# arduinoNano.net
KiCad netlist of a schematic drawn in Altium Designer
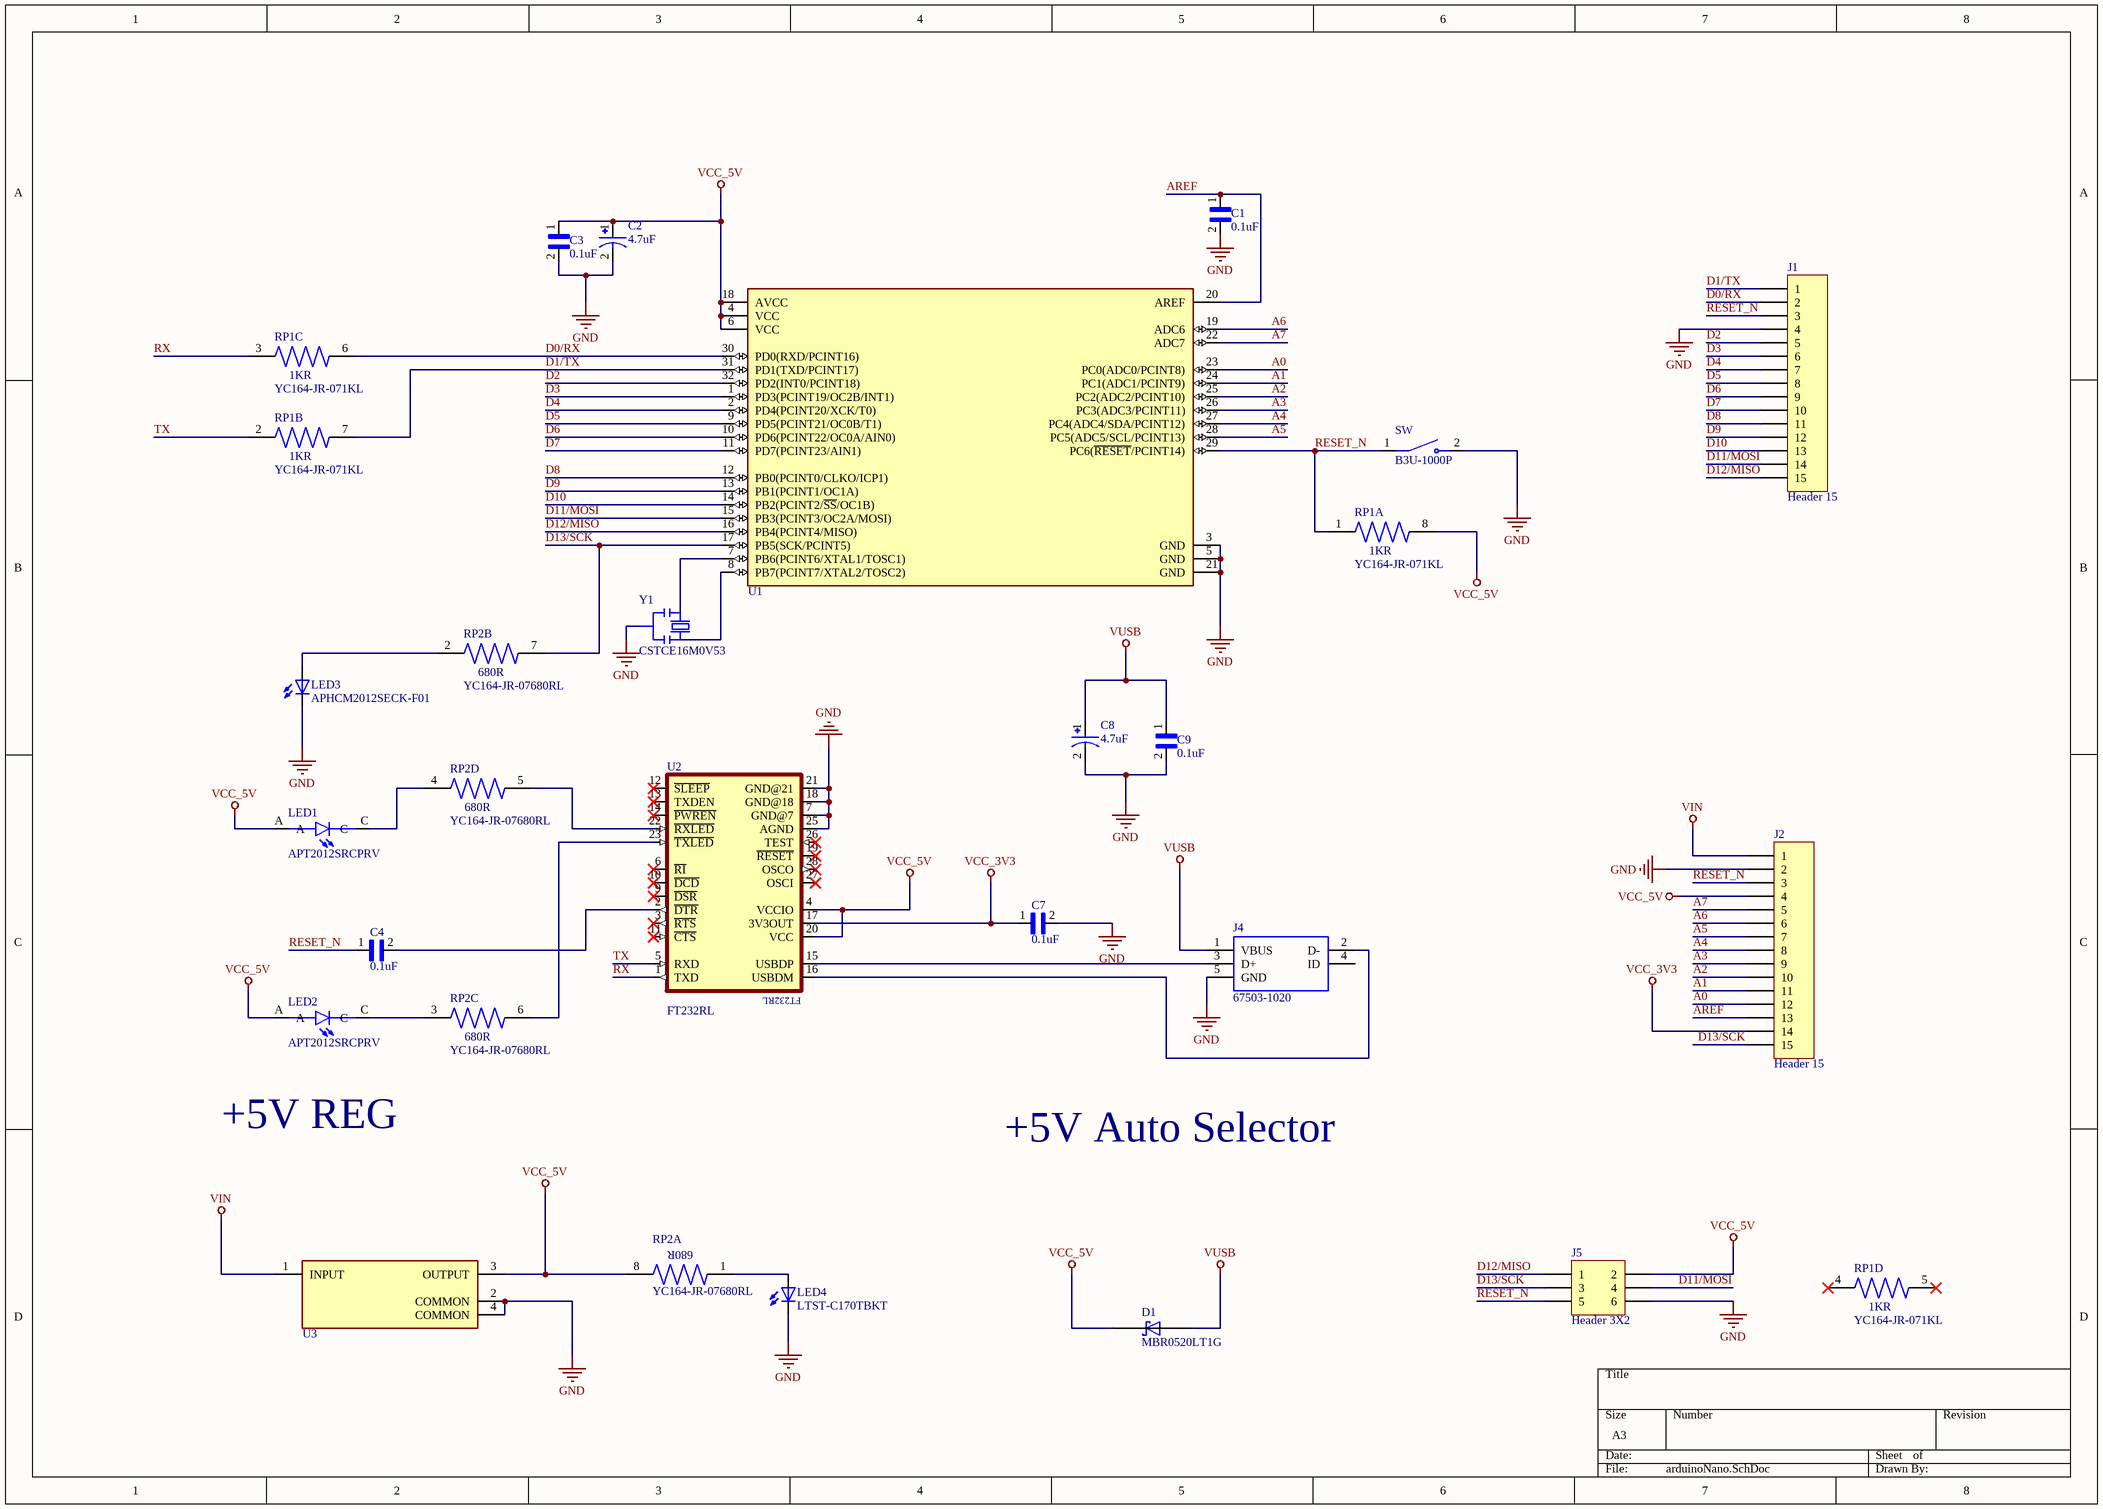
[diagram p0: arduinoNano.SchDoc]

(export (version "E")
  (design (tool "Eeschema 10.0.6"))
  (components
    (comp (ref "C1")
      (value "0.1uF")
      (footprint "arduino_nano:CAPC2012X88N")
      (description "SMD 0805 CERAMIC X7R -55^+125 100 NF +/-10? 50V")
      (fields (field (name "MF") "{'manufacturer': u'KEMET'}") (field (name "MP") "C0805C104K5RACTU"))
      (libsource (lib "arduino_nano") (part "C0805C104K5RACTU"))
    )
    (comp (ref "C2")
      (value "4.7uF")
      (footprint "arduino_nano:CAPMP3216X180N")
      (description "4.7ÂµF Molded Tantalum Capacitors 25V 1206 (3216 Metric) 6Ohm")
      (fields (field (name "MF") "{'manufacturer': u'KEMET'}") (field (name "MP") "T491A475K010AT"))
      (libsource (lib "arduino_nano") (part "T491A475K010AT"))
    )
    (comp (ref "C3")
      (value "0.1uF")
      (footprint "arduino_nano:CAPC2012X88N")
      (description "SMD 0805 CERAMIC X7R -55^+125 100 NF +/-10? 50V")
      (fields (field (name "MF") "{'manufacturer': u'KEMET'}") (field (name "MP") "C0805C104K5RACTU"))
      (libsource (lib "arduino_nano") (part "C0805C104K5RACTU"))
    )
    (comp (ref "C4")
      (value "0.1uF")
      (footprint "arduino_nano:CAPC2012X88N")
      (description "SMD 0805 CERAMIC X7R -55^+125 100 NF +/-10? 50V")
      (fields (field (name "MF") "{'manufacturer': u'KEMET'}") (field (name "MP") "C0805C104K5RACTU"))
      (libsource (lib "") (part "C0805C104K5RACTU_1"))
    )
    (comp (ref "C7")
      (value "0.1uF")
      (footprint "arduino_nano:CAPC2012X88N")
      (description "SMD 0805 CERAMIC X7R -55^+125 100 NF +/-10? 50V")
      (fields (field (name "MF") "{'manufacturer': u'KEMET'}") (field (name "MP") "C0805C104K5RACTU"))
      (libsource (lib "") (part "C0805C104K5RACTU_1"))
    )
    (comp (ref "C8")
      (value "4.7uF")
      (footprint "arduino_nano:CAPMP3216X180N")
      (description "4.7ÂµF Molded Tantalum Capacitors 25V 1206 (3216 Metric) 6Ohm")
      (fields (field (name "MF") "{'manufacturer': u'KEMET'}") (field (name "MP") "T491A475K010AT"))
      (libsource (lib "arduino_nano") (part "T491A475K010AT"))
    )
    (comp (ref "C9")
      (value "0.1uF")
      (footprint "arduino_nano:CAPC2012X88N")
      (description "SMD 0805 CERAMIC X7R -55^+125 100 NF +/-10? 50V")
      (fields (field (name "MF") "{'manufacturer': u'KEMET'}") (field (name "MP") "C0805C104K5RACTU"))
      (libsource (lib "arduino_nano") (part "C0805C104K5RACTU"))
    )
    (comp (ref "D1")
      (value "MBR0520LT1G")
      (footprint "arduino_nano:SOD3716X117(SOD-123)")
      (description "Surface Mount Schottky Power Rectifier Plastic SODâˆ’123 Package")
      (fields (field (name "MF") "{'manufacturer': u'ON Semiconductor'}"))
      (libsource (lib "arduino_nano") (part "MBR0520LT1G"))
    )
    (comp (ref "J1")
      (value "Header 15")
      (footprint "HDR1X15")
      (description "Header, 15-Pin")
      (fields (field (name "PUBLISHER") "Altium Limited"))
      (libsource (lib "Miscellaneous Connectors") (part "Header 15"))
    )
    (comp (ref "J2")
      (value "Header 15")
      (footprint "HDR1X15")
      (description "Header, 15-Pin")
      (fields (field (name "PUBLISHER") "Altium Limited"))
      (libsource (lib "Miscellaneous Connectors") (part "Header 15"))
    )
    (comp (ref "J4")
      (value "67503-1020")
      (footprint "arduino_nano:67503-1020")
      (fields (field (name "MF") "{'manufacturer': u'Molex'}"))
      (libsource (lib "arduino_nano") (part "67503-1020"))
    )
    (comp (ref "J5")
      (value "Header 3X2")
      (footprint "HDR2X3")
      (description "Header, 3-Pin, Dual row")
      (fields (field (name "PUBLISHER") "Altium Limited"))
      (libsource (lib "Miscellaneous Connectors") (part "Header 3X2"))
    )
    (comp (ref "LED1")
      (value "APT2012SRCPRV")
      (footprint "arduino_nano:LEDC2012X75N")
      (description "2.0X1.2MM,RED SMD LED")
      (fields (field (name "MF") "{'manufacturer': u'Kingbright'}"))
      (libsource (lib "arduino_nano") (part "APT2012SRCPRV"))
    )
    (comp (ref "LED2")
      (value "APT2012SRCPRV")
      (footprint "arduino_nano:LEDC2012X75N")
      (description "2.0X1.2MM,RED SMD LED")
      (fields (field (name "MF") "{'manufacturer': u'Kingbright'}"))
      (libsource (lib "arduino_nano") (part "APT2012SRCPRV"))
    )
    (comp (ref "LED3")
      (value "APHCM2012SECK-F01")
      (footprint "arduino_nano:DIOC200X125X110")
      (description "Green 2 x 1.25 x 1.1 mm 130Â° Water Clear 35 mcd 2 V Surface Mount LED")
      (fields (field (name "MF") "{'manufacturer': u'Lite-On Inc.'}") (field (name "MP") "LTST-C170TBKT"))
      (libsource (lib "arduino_nano") (part "LTST-C170TBKT"))
    )
    (comp (ref "LED4")
      (value "LTST-C170TBKT")
      (footprint "arduino_nano:DIOC200X125X110")
      (description "Green 2 x 1.25 x 1.1 mm 130Â° Water Clear 35 mcd 2 V Surface Mount LED")
      (fields (field (name "MF") "{'manufacturer': u'Lite-On Inc.'}"))
      (libsource (lib "arduino_nano") (part "LTST-C170TBKT"))
    )
    (comp (ref "RP1")
      (value "YC164-JR-071KL")
      (footprint "RESCAXE80P320X160X70-8N")
      (description "Res Thick Film Array 100 Ohm 5% ?200ppm/C ISOL Epoxy 8-Pin 1206(4 X 0603) Convex SMD T/R")
      (libsource (lib "arduino_nano") (part "YC164-JR-071KL"))
    )
    (comp (ref "RP2")
      (value "YC164-JR-07680RL")
      (footprint "RESCAXE80P320X160X70-8N")
      (description "Res Thick Film Array 100 Ohm 5% ?200ppm/C ISOL Epoxy 8-Pin 1206(4 X 0603) Convex SMD T/R")
      (libsource (lib "arduino_nano") (part "YC164-JR-07680RL"))
    )
    (comp (ref "SW")
      (value "B3U-1000P")
      (footprint "arduino_nano:SW_B3U-1000P")
      (description "Switch Tactile N.O. SPST Round Button Gull Wing 0.05A 12VDC 1.5N SMD Embossed T/R")
      (fields (field (name "MF") "{'manufacturer': u'Omron'}"))
      (libsource (lib "arduino_nano") (part "B3U-1000P"))
    )
    (comp (ref "U1")
      (value "ATMEGA168-20AU")
      (footprint "Microchip_32A_IPC_A")
      (libsource (lib "arduino_nano") (part "ATMEGA168-20AU"))
    )
    (comp (ref "U2")
      (value "FT232RL")
      (footprint "arduino_nano:SSOP28-0.65-10.2X5.2MM")
      (fields (field (name "MF") "{'manufacturer': u'FTDI, Future'}"))
      (libsource (lib "arduino_nano") (part "FT232RL"))
    )
    (comp (ref "U3")
      (value "UA78M05CDCYRG3")
      (footprint "Texas_Instruments_DCY0004A_IPC_A")
      (libsource (lib "arduino_nano") (part "UA78M05CDCYRG3"))
    )
    (comp (ref "Y1")
      (value "CSTCE16M0V53")
      (footprint "arduino_nano:CSTCE16M0V53")
      (description "<b>CSTCE16M0V53</b> Ceramic Resonator (CERALOCK) 16 MHz Chip Type")
      (fields (field (name "MF") "{'manufacturer': u'Murata Electronics'}"))
      (libsource (lib "arduino_nano") (part "CSTCE16M0V53"))
    )
  )
  (nets
    (net (code "1") (name "/A0") (class "Default")
      (node (ref "J2") (pin "12") (pinfunction "12_12") (pintype "passive"))
      (node (ref "U1") (pin "23") (pinfunction "PC0(ADC0/PCINT8)_23") (pintype "bidirectional"))
    )
    (net (code "2") (name "/A1") (class "Default")
      (node (ref "J2") (pin "11") (pinfunction "11_11") (pintype "passive"))
      (node (ref "U1") (pin "24") (pinfunction "PC1(ADC1/PCINT9)_24") (pintype "bidirectional"))
    )
    (net (code "3") (name "/A2") (class "Default")
      (node (ref "J2") (pin "10") (pinfunction "10_10") (pintype "passive"))
      (node (ref "U1") (pin "25") (pinfunction "PC2(ADC2/PCINT10)_25") (pintype "bidirectional"))
    )
    (net (code "4") (name "/A3") (class "Default")
      (node (ref "J2") (pin "9") (pinfunction "9_9") (pintype "passive"))
      (node (ref "U1") (pin "26") (pinfunction "PC3(ADC3/PCINT11)_26") (pintype "bidirectional"))
    )
    (net (code "5") (name "/A4") (class "Default")
      (node (ref "J2") (pin "8") (pinfunction "8_8") (pintype "passive"))
      (node (ref "U1") (pin "27") (pinfunction "PC4(ADC4/SDA/PCINT12)_27") (pintype "bidirectional"))
    )
    (net (code "6") (name "/A5") (class "Default")
      (node (ref "J2") (pin "7") (pinfunction "7_7") (pintype "passive"))
      (node (ref "U1") (pin "28") (pinfunction "PC5(ADC5/SCL/PCINT13)_28") (pintype "bidirectional"))
    )
    (net (code "7") (name "/A6") (class "Default")
      (node (ref "J2") (pin "6") (pinfunction "6_6") (pintype "passive"))
      (node (ref "U1") (pin "19") (pinfunction "ADC6_19") (pintype "bidirectional"))
    )
    (net (code "8") (name "/A7") (class "Default")
      (node (ref "J2") (pin "5") (pinfunction "5_5") (pintype "passive"))
      (node (ref "U1") (pin "22") (pinfunction "ADC7_22") (pintype "bidirectional"))
    )
    (net (code "9") (name "/AREF") (class "Default")
      (node (ref "C1") (pin "1") (pinfunction "1_1") (pintype "passive"))
      (node (ref "J2") (pin "13") (pinfunction "13_13") (pintype "passive"))
      (node (ref "U1") (pin "20") (pinfunction "AREF_20") (pintype "passive"))
    )
    (net (code "10") (name "/D0{slash}RX") (class "Default")
      (node (ref "J1") (pin "2") (pinfunction "2_2") (pintype "passive"))
      (node (ref "RP1") (pin "6") (pinfunction "6_6") (pintype "passive"))
      (node (ref "U1") (pin "30") (pinfunction "PD0(RXD/PCINT16)_30") (pintype "bidirectional"))
    )
    (net (code "11") (name "/D1{slash}TX") (class "Default")
      (node (ref "J1") (pin "1") (pinfunction "1_1") (pintype "passive"))
      (node (ref "RP1") (pin "7") (pinfunction "7_7") (pintype "passive"))
      (node (ref "U1") (pin "31") (pinfunction "PD1(TXD/PCINT17)_31") (pintype "bidirectional"))
    )
    (net (code "12") (name "/D2") (class "Default")
      (node (ref "J1") (pin "5") (pinfunction "5_5") (pintype "passive"))
      (node (ref "U1") (pin "32") (pinfunction "PD2(INT0/PCINT18)_32") (pintype "bidirectional"))
    )
    (net (code "13") (name "/D3") (class "Default")
      (node (ref "J1") (pin "6") (pinfunction "6_6") (pintype "passive"))
      (node (ref "U1") (pin "1") (pinfunction "PD3(PCINT19/OC2B/INT1)_1") (pintype "bidirectional"))
    )
    (net (code "14") (name "/D4") (class "Default")
      (node (ref "J1") (pin "7") (pinfunction "7_7") (pintype "passive"))
      (node (ref "U1") (pin "2") (pinfunction "PD4(PCINT20/XCK/T0)_2") (pintype "bidirectional"))
    )
    (net (code "15") (name "/D5") (class "Default")
      (node (ref "J1") (pin "8") (pinfunction "8_8") (pintype "passive"))
      (node (ref "U1") (pin "9") (pinfunction "PD5(PCINT21/OC0B/T1)_9") (pintype "bidirectional"))
    )
    (net (code "16") (name "/D6") (class "Default")
      (node (ref "J1") (pin "9") (pinfunction "9_9") (pintype "passive"))
      (node (ref "U1") (pin "10") (pinfunction "PD6(PCINT22/OC0A/AIN0)_10") (pintype "bidirectional"))
    )
    (net (code "17") (name "/D7") (class "Default")
      (node (ref "J1") (pin "10") (pinfunction "10_10") (pintype "passive"))
      (node (ref "U1") (pin "11") (pinfunction "PD7(PCINT23/AIN1)_11") (pintype "bidirectional"))
    )
    (net (code "18") (name "/D8") (class "Default")
      (node (ref "J1") (pin "11") (pinfunction "11_11") (pintype "passive"))
      (node (ref "U1") (pin "12") (pinfunction "PB0(PCINT0/CLKO/ICP1)_12") (pintype "bidirectional"))
    )
    (net (code "19") (name "/D9") (class "Default")
      (node (ref "J1") (pin "12") (pinfunction "12_12") (pintype "passive"))
      (node (ref "U1") (pin "13") (pinfunction "PB1(PCINT1/OC1A)_13") (pintype "bidirectional"))
    )
    (net (code "20") (name "/D10") (class "Default")
      (node (ref "J1") (pin "13") (pinfunction "13_13") (pintype "passive"))
      (node (ref "U1") (pin "14") (pinfunction "PB2(PCINT2/~{SS}/OC1B)_14") (pintype "bidirectional"))
    )
    (net (code "21") (name "/D11{slash}MOSI") (class "Default")
      (node (ref "J1") (pin "14") (pinfunction "14_14") (pintype "passive"))
      (node (ref "J5") (pin "4") (pinfunction "4_4") (pintype "passive"))
      (node (ref "U1") (pin "15") (pinfunction "PB3(PCINT3/OC2A/MOSI)_15") (pintype "bidirectional"))
    )
    (net (code "22") (name "/D12{slash}MISO") (class "Default")
      (node (ref "J1") (pin "15") (pinfunction "15_15") (pintype "passive"))
      (node (ref "J5") (pin "1") (pinfunction "1_1") (pintype "passive"))
      (node (ref "U1") (pin "16") (pinfunction "PB4(PCINT4/MISO)_16") (pintype "bidirectional"))
    )
    (net (code "23") (name "/D13{slash}SCK") (class "Default")
      (node (ref "J2") (pin "15") (pinfunction "15_15") (pintype "passive"))
      (node (ref "J5") (pin "3") (pinfunction "3_3") (pintype "passive"))
      (node (ref "RP2") (pin "7") (pinfunction "7_7") (pintype "passive"))
      (node (ref "U1") (pin "17") (pinfunction "PB5(SCK/PCINT5)_17") (pintype "bidirectional"))
    )
    (net (code "24") (name "/RESET_N") (class "Default")
      (node (ref "C4") (pin "1") (pinfunction "1_1") (pintype "passive"))
      (node (ref "J1") (pin "3") (pinfunction "3_3") (pintype "passive"))
      (node (ref "J2") (pin "3") (pinfunction "3_3") (pintype "passive"))
      (node (ref "J5") (pin "5") (pinfunction "5_5") (pintype "passive"))
      (node (ref "RP1") (pin "1") (pinfunction "1_1") (pintype "passive"))
      (node (ref "SW") (pin "1") (pinfunction "1_1") (pintype "passive"))
      (node (ref "U1") (pin "29") (pinfunction "PC6(~{RESET}/PCINT14)_29") (pintype "bidirectional"))
    )
    (net (code "25") (name "/RX") (class "Default")
      (node (ref "RP1") (pin "3") (pinfunction "3_3") (pintype "passive"))
      (node (ref "U2") (pin "1") (pinfunction "TXD_1") (pintype "output"))
    )
    (net (code "26") (name "/TX") (class "Default")
      (node (ref "RP1") (pin "2") (pinfunction "2_2") (pintype "passive"))
      (node (ref "U2") (pin "5") (pinfunction "RXD_5") (pintype "input"))
    )
    (net (code "27") (name "GND") (class "Default")
      (node (ref "C1") (pin "2") (pinfunction "2_2") (pintype "passive"))
      (node (ref "C2") (pin "2") (pinfunction "2_2") (pintype "passive"))
      (node (ref "C3") (pin "2") (pinfunction "2_2") (pintype "passive"))
      (node (ref "C7") (pin "2") (pinfunction "2_2") (pintype "passive"))
      (node (ref "C8") (pin "2") (pinfunction "2_2") (pintype "passive"))
      (node (ref "C9") (pin "2") (pinfunction "2_2") (pintype "passive"))
      (node (ref "J1") (pin "4") (pinfunction "4_4") (pintype "passive"))
      (node (ref "J2") (pin "2") (pinfunction "2_2") (pintype "passive"))
      (node (ref "J4") (pin "5") (pinfunction "GND_5") (pintype "passive"))
      (node (ref "J5") (pin "6") (pinfunction "6_6") (pintype "passive"))
      (node (ref "LED3") (pin "NEG") (pinfunction "NEG_NEG") (pintype "passive"))
      (node (ref "LED4") (pin "NEG") (pinfunction "NEG_NEG") (pintype "passive"))
      (node (ref "SW") (pin "2") (pinfunction "2_2") (pintype "passive"))
      (node (ref "U1") (pin "21") (pinfunction "GND_21") (pintype "power_in"))
      (node (ref "U1") (pin "3") (pinfunction "GND_3") (pintype "power_in"))
      (node (ref "U1") (pin "5") (pinfunction "GND_5") (pintype "power_in"))
      (node (ref "U2") (pin "18") (pinfunction "GND@18_18") (pintype "power_in"))
      (node (ref "U2") (pin "21") (pinfunction "GND@21_21") (pintype "power_in"))
      (node (ref "U2") (pin "25") (pinfunction "AGND_25") (pintype "power_in"))
      (node (ref "U2") (pin "7") (pinfunction "GND@7_7") (pintype "power_in"))
      (node (ref "U3") (pin "2") (pinfunction "COMMON_2") (pintype "power_in"))
      (node (ref "U3") (pin "4") (pinfunction "COMMON_4") (pintype "power_in"))
      (node (ref "Y1") (pin "2") (pinfunction "2_2") (pintype "passive"))
    )
    (net (code "28") (name "Net-(J4-D+)") (class "Default")
      (node (ref "J4") (pin "3") (pinfunction "D+_3") (pintype "passive"))
      (node (ref "U2") (pin "15") (pinfunction "USBDP_15") (pintype "bidirectional"))
    )
    (net (code "29") (name "Net-(J4-D-)") (class "Default")
      (node (ref "J4") (pin "2") (pinfunction "D-_2") (pintype "passive"))
      (node (ref "U2") (pin "16") (pinfunction "USBDM_16") (pintype "bidirectional"))
    )
    (net (code "30") (name "Net-(LED1-PadC)") (class "Default")
      (node (ref "LED1") (pin "C") (pinfunction "C_C") (pintype "passive"))
      (node (ref "RP2") (pin "4") (pinfunction "4_4") (pintype "passive"))
    )
    (net (code "31") (name "Net-(LED2-PadC)") (class "Default")
      (node (ref "LED2") (pin "C") (pinfunction "C_C") (pintype "passive"))
      (node (ref "RP2") (pin "3") (pinfunction "3_3") (pintype "passive"))
    )
    (net (code "32") (name "Net-(LED3-PadPOS)") (class "Default")
      (node (ref "LED3") (pin "POS") (pinfunction "POS_POS") (pintype "passive"))
      (node (ref "RP2") (pin "2") (pinfunction "2_2") (pintype "passive"))
    )
    (net (code "33") (name "Net-(LED4-PadPOS)") (class "Default")
      (node (ref "LED4") (pin "POS") (pinfunction "POS_POS") (pintype "passive"))
      (node (ref "RP2") (pin "1") (pinfunction "1_1") (pintype "passive"))
    )
    (net (code "34") (name "Net-(U1-PB6(PCINT6{slash}XTAL1{slash}TOSC1))") (class "Default")
      (node (ref "U1") (pin "7") (pinfunction "PB6(PCINT6/XTAL1/TOSC1)_7") (pintype "bidirectional"))
      (node (ref "Y1") (pin "1") (pinfunction "1_1") (pintype "passive"))
    )
    (net (code "35") (name "Net-(U1-PB7(PCINT7{slash}XTAL2{slash}TOSC2))") (class "Default")
      (node (ref "U1") (pin "8") (pinfunction "PB7(PCINT7/XTAL2/TOSC2)_8") (pintype "bidirectional"))
      (node (ref "Y1") (pin "3") (pinfunction "3_3") (pintype "passive"))
    )
    (net (code "36") (name "Net-(U2-~{DTR})") (class "Default")
      (node (ref "C4") (pin "2") (pinfunction "2_2") (pintype "passive"))
      (node (ref "U2") (pin "2") (pinfunction "~{DTR}_2") (pintype "output"))
    )
    (net (code "37") (name "Net-(U2-~{RXLED})") (class "Default")
      (node (ref "RP2") (pin "5") (pinfunction "5_5") (pintype "passive"))
      (node (ref "U2") (pin "22") (pinfunction "~{RXLED}_22") (pintype "input"))
    )
    (net (code "38") (name "Net-(U2-~{TXLED})") (class "Default")
      (node (ref "RP2") (pin "6") (pinfunction "6_6") (pintype "passive"))
      (node (ref "U2") (pin "23") (pinfunction "~{TXLED}_23") (pintype "input"))
    )
    (net (code "39") (name "VCC_3V3") (class "Default")
      (node (ref "C7") (pin "1") (pinfunction "1_1") (pintype "passive"))
      (node (ref "J2") (pin "14") (pinfunction "14_14") (pintype "passive"))
      (node (ref "U2") (pin "17") (pinfunction "3V3OUT_17") (pintype "power_in"))
    )
    (net (code "40") (name "VCC_5V") (class "Default")
      (node (ref "C2") (pin "1") (pinfunction "1_1") (pintype "passive"))
      (node (ref "C3") (pin "1") (pinfunction "1_1") (pintype "passive"))
      (node (ref "D1") (pin "1") (pinfunction "C_1") (pintype "passive"))
      (node (ref "J2") (pin "4") (pinfunction "4_4") (pintype "passive"))
      (node (ref "J5") (pin "2") (pinfunction "2_2") (pintype "passive"))
      (node (ref "LED1") (pin "A") (pinfunction "A_A") (pintype "passive"))
      (node (ref "LED2") (pin "A") (pinfunction "A_A") (pintype "passive"))
      (node (ref "RP1") (pin "8") (pinfunction "8_8") (pintype "passive"))
      (node (ref "RP2") (pin "8") (pinfunction "8_8") (pintype "passive"))
      (node (ref "U1") (pin "18") (pinfunction "AVCC_18") (pintype "power_in"))
      (node (ref "U1") (pin "4") (pinfunction "VCC_4") (pintype "power_in"))
      (node (ref "U1") (pin "6") (pinfunction "VCC_6") (pintype "power_in"))
      (node (ref "U2") (pin "20") (pinfunction "VCC_20") (pintype "power_in"))
      (node (ref "U2") (pin "4") (pinfunction "VCCIO_4") (pintype "power_in"))
      (node (ref "U3") (pin "3") (pinfunction "OUTPUT_3") (pintype "power_in"))
    )
    (net (code "41") (name "VIN") (class "Default")
      (node (ref "J2") (pin "1") (pinfunction "1_1") (pintype "passive"))
      (node (ref "U3") (pin "1") (pinfunction "INPUT_1") (pintype "power_in"))
    )
    (net (code "42") (name "VUSB") (class "Default")
      (node (ref "C8") (pin "1") (pinfunction "1_1") (pintype "passive"))
      (node (ref "C9") (pin "1") (pinfunction "1_1") (pintype "passive"))
      (node (ref "D1") (pin "2") (pinfunction "A_2") (pintype "passive"))
      (node (ref "J4") (pin "1") (pinfunction "VBUS_1") (pintype "passive"))
    )
    (net (code "43") (name "unconnected-(J4-ID-Pad4)") (class "Default")
      (node (ref "J4") (pin "4") (pinfunction "ID_4") (pintype "passive"))
    )
    (net (code "44") (name "unconnected-(RP1-Pad4)") (class "Default")
      (node (ref "RP1") (pin "4") (pinfunction "4_4") (pintype "passive+no_connect"))
    )
    (net (code "45") (name "unconnected-(RP1-Pad5)") (class "Default")
      (node (ref "RP1") (pin "5") (pinfunction "5_5") (pintype "passive+no_connect"))
    )
    (net (code "46") (name "unconnected-(U2-OSCI-Pad27)") (class "Default")
      (node (ref "U2") (pin "27") (pinfunction "OSCI_27") (pintype "passive+no_connect"))
    )
    (net (code "47") (name "unconnected-(U2-OSCO-Pad28)") (class "Default")
      (node (ref "U2") (pin "28") (pinfunction "OSCO_28") (pintype "output+no_connect"))
    )
    (net (code "48") (name "unconnected-(U2-TEST-Pad26)") (class "Default")
      (node (ref "U2") (pin "26") (pinfunction "TEST_26") (pintype "input+no_connect"))
    )
    (net (code "49") (name "unconnected-(U2-TXDEN-Pad13)") (class "Default")
      (node (ref "U2") (pin "13") (pinfunction "TXDEN_13") (pintype "passive+no_connect"))
    )
    (net (code "50") (name "unconnected-(U2-~{CTS}-Pad11)") (class "Default")
      (node (ref "U2") (pin "11") (pinfunction "~{CTS}_11") (pintype "input+no_connect"))
    )
    (net (code "51") (name "unconnected-(U2-~{DCD}-Pad10)") (class "Default")
      (node (ref "U2") (pin "10") (pinfunction "~{DCD}_10") (pintype "passive+no_connect"))
    )
    (net (code "52") (name "unconnected-(U2-~{DSR}-Pad9)") (class "Default")
      (node (ref "U2") (pin "9") (pinfunction "~{DSR}_9") (pintype "passive+no_connect"))
    )
    (net (code "53") (name "unconnected-(U2-~{PWREN}-Pad14)") (class "Default")
      (node (ref "U2") (pin "14") (pinfunction "~{PWREN}_14") (pintype "passive+no_connect"))
    )
    (net (code "54") (name "unconnected-(U2-~{RESET}-Pad19)") (class "Default")
      (node (ref "U2") (pin "19") (pinfunction "~{RESET}_19") (pintype "passive+no_connect"))
    )
    (net (code "55") (name "unconnected-(U2-~{RI}-Pad6)") (class "Default")
      (node (ref "U2") (pin "6") (pinfunction "~{RI}_6") (pintype "passive+no_connect"))
    )
    (net (code "56") (name "unconnected-(U2-~{RTS}-Pad3)") (class "Default")
      (node (ref "U2") (pin "3") (pinfunction "~{RTS}_3") (pintype "output+no_connect"))
    )
    (net (code "57") (name "unconnected-(U2-~{SLEEP}-Pad12)") (class "Default")
      (node (ref "U2") (pin "12") (pinfunction "~{SLEEP}_12") (pintype "passive+no_connect"))
    )
  )
)
